# habexpico.net
KiCad netlist of a schematic drawn in EAGLE
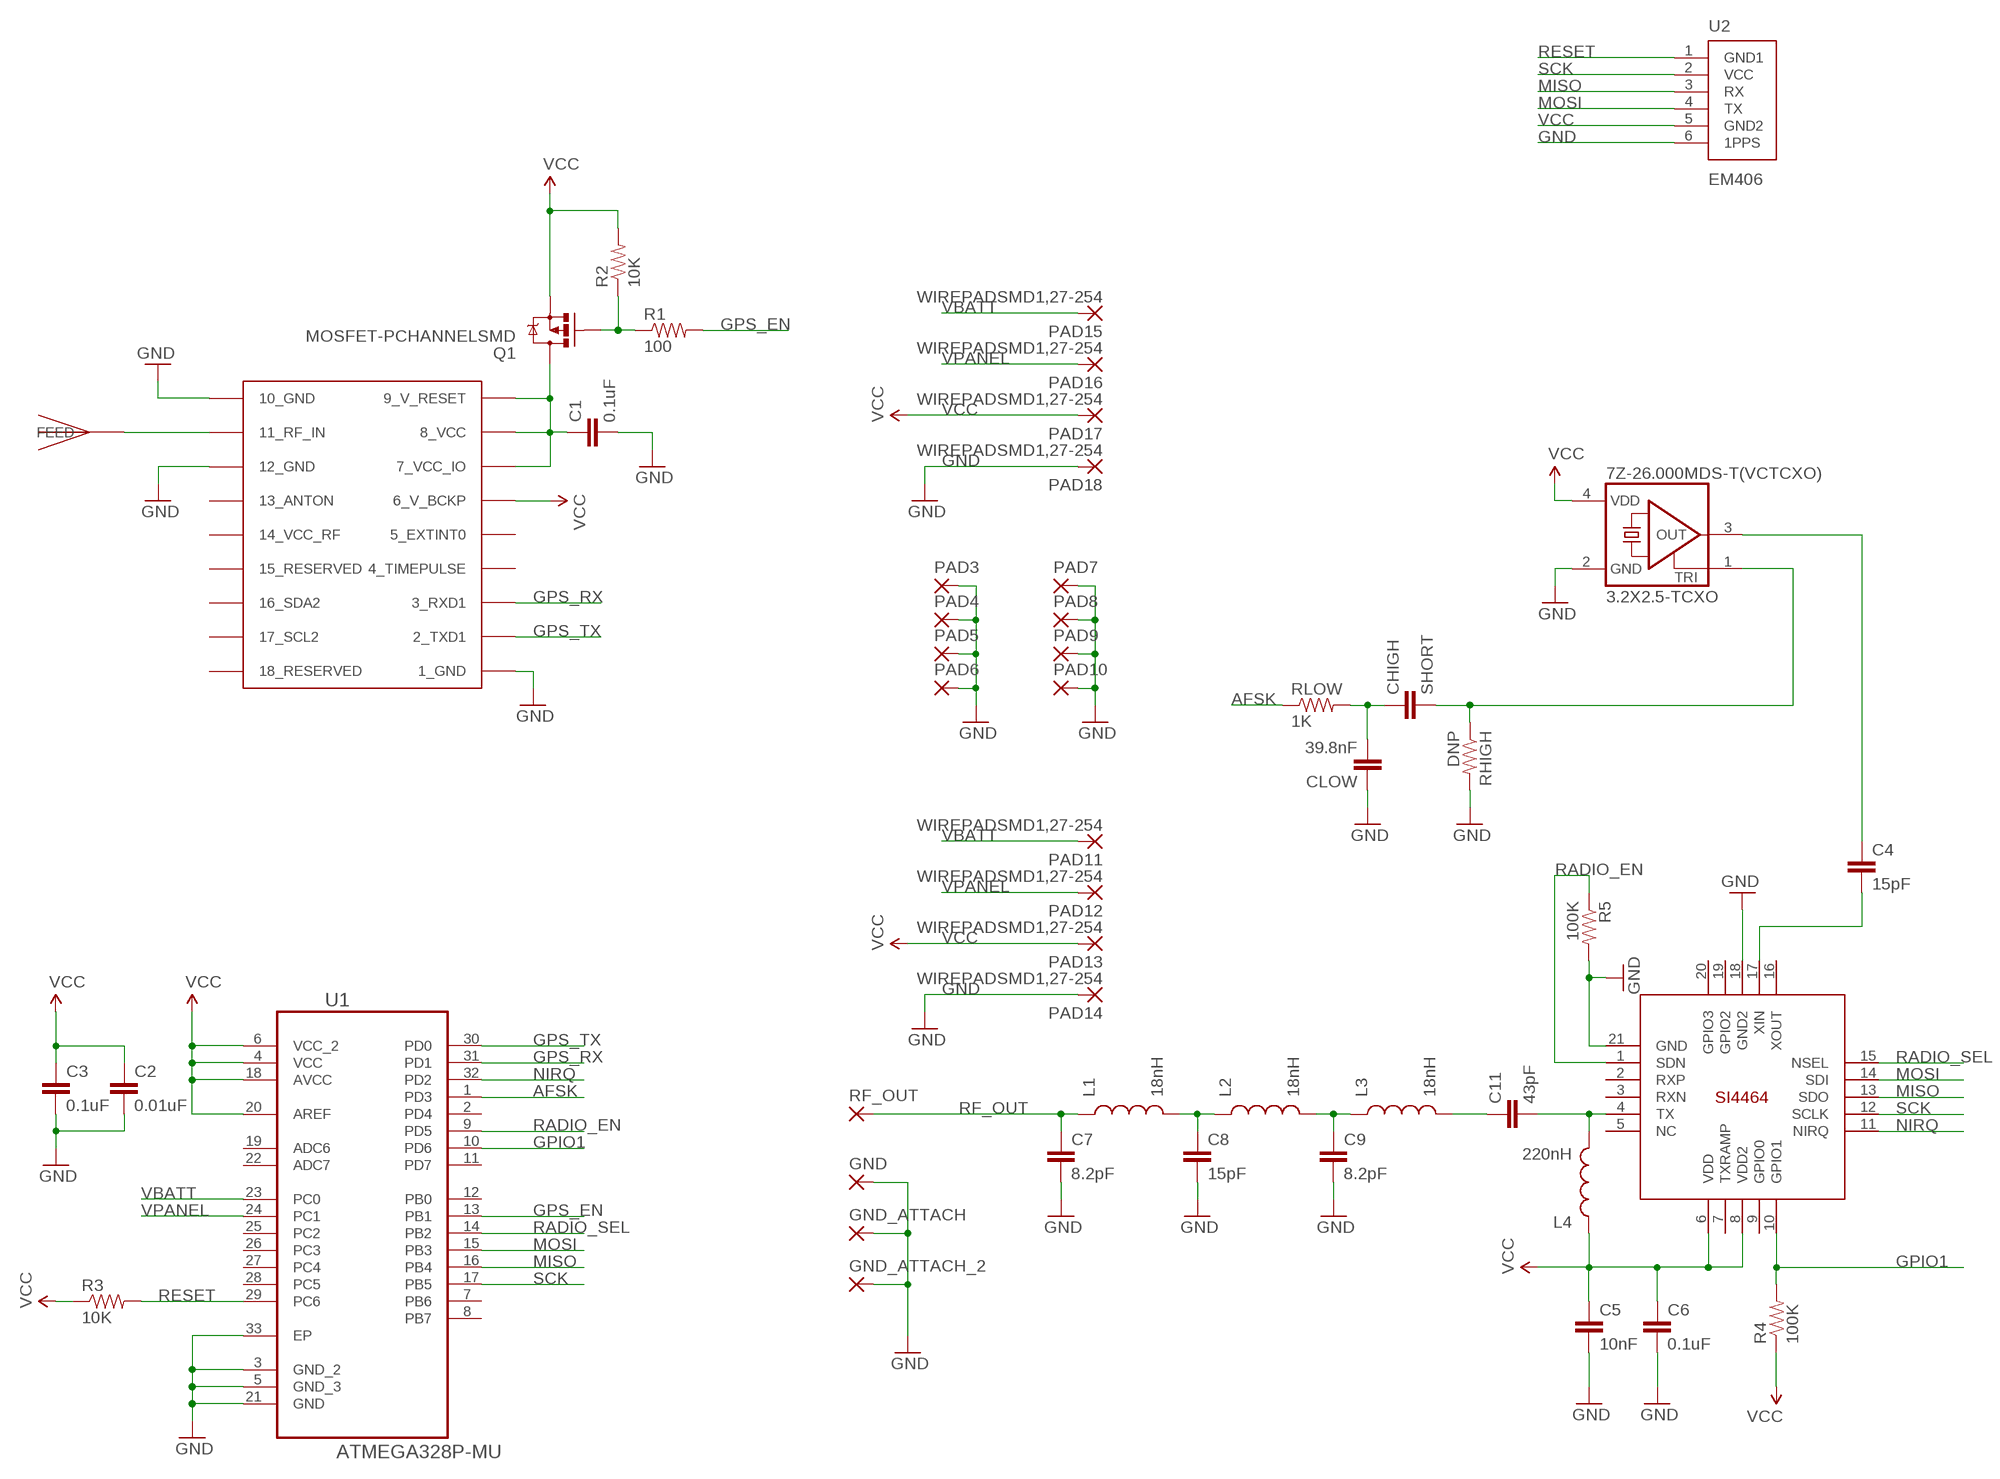
[diagram p0: schematic, sheet 1, part 1 of 2]
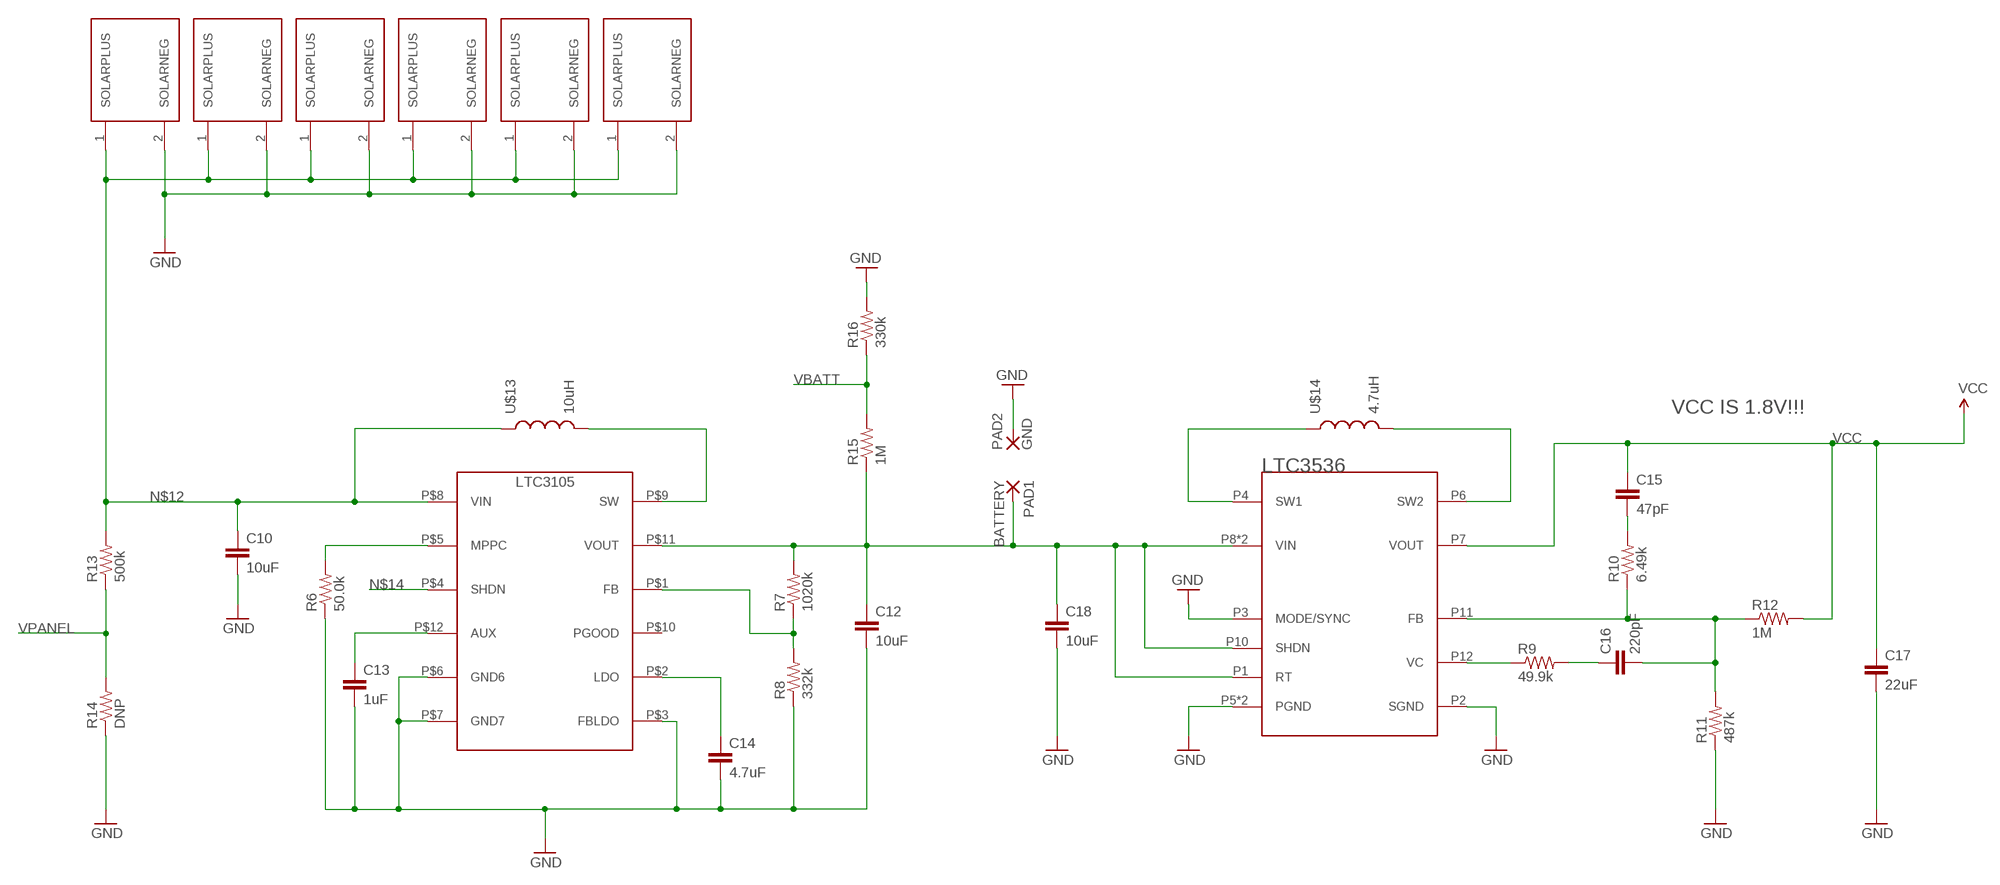
[diagram p1: schematic, sheet 1, part 2 of 2]

(export (version "E")
  (design (tool "Eeschema 10.0.6"))
  (components
    (comp (ref "7Z-26.000MDS-T(VCTCXO)")
      (value "3.2X2.5-TCXO")
      (footprint "eagle-import:3.2X2.5-TCXO")
      (libsource (lib "eagle-import") (part "3.2X2.5-TCXO"))
    )
    (comp (ref "C1")
      (value "0.1uF")
      (footprint "eagle-import:0603-CAP")
      (libsource (lib "eagle-import") (part "CAP0603-CAP"))
    )
    (comp (ref "C2")
      (value "0.01uF")
      (footprint "eagle-import:0603-CAP")
      (libsource (lib "eagle-import") (part "CAP0603-CAP"))
    )
    (comp (ref "C3")
      (value "0.1uF")
      (footprint "eagle-import:0603-CAP")
      (libsource (lib "eagle-import") (part "CAP0603-CAP"))
    )
    (comp (ref "C4")
      (value "15pF")
      (footprint "eagle-import:0603-CAP")
      (libsource (lib "eagle-import") (part "CAP0603-CAP"))
    )
    (comp (ref "C5")
      (value "10nF")
      (footprint "eagle-import:0603-CAP")
      (libsource (lib "eagle-import") (part "CAP0603-CAP"))
    )
    (comp (ref "C6")
      (value "0.1uF")
      (footprint "eagle-import:0603-CAP")
      (libsource (lib "eagle-import") (part "CAP0603-CAP"))
    )
    (comp (ref "C7")
      (value "8.2pF")
      (footprint "eagle-import:0603-CAP")
      (libsource (lib "eagle-import") (part "CAP0603-CAP"))
    )
    (comp (ref "C8")
      (value "15pF")
      (footprint "eagle-import:0603-CAP")
      (libsource (lib "eagle-import") (part "CAP0603-CAP"))
    )
    (comp (ref "C9")
      (value "8.2pF")
      (footprint "eagle-import:0603-CAP")
      (libsource (lib "eagle-import") (part "CAP0603-CAP"))
    )
    (comp (ref "C10")
      (value "10uF")
      (footprint "eagle-import:0805")
      (libsource (lib "eagle-import") (part "CAP0805"))
    )
    (comp (ref "C11")
      (value "43pF")
      (footprint "eagle-import:0603-CAP")
      (libsource (lib "eagle-import") (part "CAP0603-CAP"))
    )
    (comp (ref "C12")
      (value "10uF")
      (footprint "eagle-import:0805")
      (libsource (lib "eagle-import") (part "CAP0805"))
    )
    (comp (ref "C13")
      (value "1uF")
      (footprint "eagle-import:0603-CAP")
      (libsource (lib "eagle-import") (part "CAP0603-CAP"))
    )
    (comp (ref "C14")
      (value "4.7uF")
      (footprint "eagle-import:0603-CAP")
      (libsource (lib "eagle-import") (part "CAP0603-CAP"))
    )
    (comp (ref "C15")
      (value "47pF")
      (footprint "eagle-import:0603-CAP")
      (libsource (lib "eagle-import") (part "CAP0603-CAP"))
    )
    (comp (ref "C16")
      (value "220pF")
      (footprint "eagle-import:0603-CAP")
      (libsource (lib "eagle-import") (part "CAP0603-CAP"))
    )
    (comp (ref "C17")
      (value "22uF")
      (footprint "eagle-import:0603-CAP")
      (libsource (lib "eagle-import") (part "CAP0603-CAP"))
    )
    (comp (ref "C18")
      (value "10uF")
      (footprint "eagle-import:0805")
      (libsource (lib "eagle-import") (part "CAP0805"))
    )
    (comp (ref "CHIGH")
      (value "SHORT")
      (footprint "eagle-import:0603-CAP")
      (libsource (lib "eagle-import") (part "CAP0603-CAP"))
    )
    (comp (ref "CLOW")
      (value "39.8nF")
      (footprint "eagle-import:0603-CAP")
      (libsource (lib "eagle-import") (part "CAP0603-CAP"))
    )
    (comp (ref "GND")
      (value "SMD5")
      (footprint "eagle-import:SMD2,54-5,08")
      (libsource (lib "eagle-import") (part "SMD5"))
    )
    (comp (ref "GND_ATTACH")
      (value "SMD2")
      (footprint "eagle-import:SMD1,27-2,54")
      (libsource (lib "eagle-import") (part "SMD2"))
    )
    (comp (ref "GND_ATTACH_2")
      (value "SMD2")
      (footprint "eagle-import:SMD1,27-2,54")
      (libsource (lib "eagle-import") (part "SMD2"))
    )
    (comp (ref "L1")
      (value "18nH")
      (footprint "eagle-import:0603")
      (libsource (lib "eagle-import") (part "INDUCTOR0603"))
    )
    (comp (ref "L2")
      (value "18nH")
      (footprint "eagle-import:0603")
      (libsource (lib "eagle-import") (part "INDUCTOR0603"))
    )
    (comp (ref "L3")
      (value "18nH")
      (footprint "eagle-import:0603")
      (libsource (lib "eagle-import") (part "INDUCTOR0603"))
    )
    (comp (ref "L4")
      (value "220nH")
      (footprint "eagle-import:0603")
      (libsource (lib "eagle-import") (part "INDUCTOR0603"))
    )
    (comp (ref "PAD1")
      (value "BATTERY")
      (footprint "eagle-import:5-2,5")
      (libsource (lib "eagle-import") (part "WIREPADSMD5-2,5"))
    )
    (comp (ref "PAD2")
      (value "GND")
      (footprint "eagle-import:5-2,5")
      (libsource (lib "eagle-import") (part "WIREPADSMD5-2,5"))
    )
    (comp (ref "PAD3")
      (value "SMD2")
      (footprint "eagle-import:SMD1,27-2,54")
      (libsource (lib "eagle-import") (part "SMD2"))
    )
    (comp (ref "PAD4")
      (value "SMD2")
      (footprint "eagle-import:SMD1,27-2,54")
      (libsource (lib "eagle-import") (part "SMD2"))
    )
    (comp (ref "PAD5")
      (value "SMD2")
      (footprint "eagle-import:SMD1,27-2,54")
      (libsource (lib "eagle-import") (part "SMD2"))
    )
    (comp (ref "PAD6")
      (value "SMD2")
      (footprint "eagle-import:SMD1,27-2,54")
      (libsource (lib "eagle-import") (part "SMD2"))
    )
    (comp (ref "PAD7")
      (value "SMD2")
      (footprint "eagle-import:SMD1,27-2,54")
      (libsource (lib "eagle-import") (part "SMD2"))
    )
    (comp (ref "PAD8")
      (value "SMD2")
      (footprint "eagle-import:SMD1,27-2,54")
      (libsource (lib "eagle-import") (part "SMD2"))
    )
    (comp (ref "PAD9")
      (value "SMD2")
      (footprint "eagle-import:SMD1,27-2,54")
      (libsource (lib "eagle-import") (part "SMD2"))
    )
    (comp (ref "PAD10")
      (value "SMD2")
      (footprint "eagle-import:SMD1,27-2,54")
      (libsource (lib "eagle-import") (part "SMD2"))
    )
    (comp (ref "PAD11")
      (value "WIREPADSMD1,27-254")
      (footprint "eagle-import:SMD1,27-2,54")
      (libsource (lib "eagle-import") (part "WIREPADSMD1,27-254"))
    )
    (comp (ref "PAD12")
      (value "WIREPADSMD1,27-254")
      (footprint "eagle-import:SMD1,27-2,54")
      (libsource (lib "eagle-import") (part "WIREPADSMD1,27-254"))
    )
    (comp (ref "PAD13")
      (value "WIREPADSMD1,27-254")
      (footprint "eagle-import:SMD1,27-2,54")
      (libsource (lib "eagle-import") (part "WIREPADSMD1,27-254"))
    )
    (comp (ref "PAD14")
      (value "WIREPADSMD1,27-254")
      (footprint "eagle-import:SMD1,27-2,54")
      (libsource (lib "eagle-import") (part "WIREPADSMD1,27-254"))
    )
    (comp (ref "PAD15")
      (value "WIREPADSMD1,27-254")
      (footprint "eagle-import:SMD1,27-2,54")
      (libsource (lib "eagle-import") (part "WIREPADSMD1,27-254"))
    )
    (comp (ref "PAD16")
      (value "WIREPADSMD1,27-254")
      (footprint "eagle-import:SMD1,27-2,54")
      (libsource (lib "eagle-import") (part "WIREPADSMD1,27-254"))
    )
    (comp (ref "PAD17")
      (value "WIREPADSMD1,27-254")
      (footprint "eagle-import:SMD1,27-2,54")
      (libsource (lib "eagle-import") (part "WIREPADSMD1,27-254"))
    )
    (comp (ref "PAD18")
      (value "WIREPADSMD1,27-254")
      (footprint "eagle-import:SMD1,27-2,54")
      (libsource (lib "eagle-import") (part "WIREPADSMD1,27-254"))
    )
    (comp (ref "Q1")
      (value "MOSFET-PCHANNELSMD")
      (footprint "eagle-import:SOT23-3")
      (libsource (lib "eagle-import") (part "MOSFET-PCHANNELSMD"))
    )
    (comp (ref "R1")
      (value "100")
      (footprint "eagle-import:0603-RES")
      (libsource (lib "eagle-import") (part "RESISTOR0603-RES"))
    )
    (comp (ref "R2")
      (value "10K")
      (footprint "eagle-import:0603-RES")
      (libsource (lib "eagle-import") (part "RESISTOR0603-RES"))
    )
    (comp (ref "R3")
      (value "10K")
      (footprint "eagle-import:0603-RES")
      (libsource (lib "eagle-import") (part "RESISTOR0603-RES"))
    )
    (comp (ref "R4")
      (value "100K")
      (footprint "eagle-import:0603-RES")
      (libsource (lib "eagle-import") (part "RESISTOR0603-RES"))
    )
    (comp (ref "R5")
      (value "100K")
      (footprint "eagle-import:0603-RES")
      (libsource (lib "eagle-import") (part "RESISTOR0603-RES"))
    )
    (comp (ref "R6")
      (value "50.0k")
      (footprint "eagle-import:0603-RES")
      (libsource (lib "eagle-import") (part "RESISTOR0603-RES"))
    )
    (comp (ref "R7")
      (value "1020k")
      (footprint "eagle-import:0603-RES")
      (libsource (lib "eagle-import") (part "RESISTOR0603-RES"))
    )
    (comp (ref "R8")
      (value "332k")
      (footprint "eagle-import:0603-RES")
      (libsource (lib "eagle-import") (part "RESISTOR0603-RES"))
    )
    (comp (ref "R9")
      (value "49.9k")
      (footprint "eagle-import:0603-RES")
      (libsource (lib "eagle-import") (part "RESISTOR0603-RES"))
    )
    (comp (ref "R10")
      (value "6.49k")
      (footprint "eagle-import:0603-RES")
      (libsource (lib "eagle-import") (part "RESISTOR0603-RES"))
    )
    (comp (ref "R11")
      (value "487k")
      (footprint "eagle-import:0603-RES")
      (libsource (lib "eagle-import") (part "RESISTOR0603-RES"))
    )
    (comp (ref "R12")
      (value "1M")
      (footprint "eagle-import:0603-RES")
      (libsource (lib "eagle-import") (part "RESISTOR0603-RES"))
    )
    (comp (ref "R13")
      (value "500k")
      (footprint "eagle-import:0603-RES")
      (libsource (lib "eagle-import") (part "RESISTOR0603-RES"))
    )
    (comp (ref "R14")
      (value "DNP")
      (footprint "eagle-import:0603-RES")
      (libsource (lib "eagle-import") (part "RESISTOR0603-RES"))
    )
    (comp (ref "R15")
      (value "1M")
      (footprint "eagle-import:0603-RES")
      (libsource (lib "eagle-import") (part "RESISTOR0603-RES"))
    )
    (comp (ref "R16")
      (value "330k")
      (footprint "eagle-import:0603-RES")
      (libsource (lib "eagle-import") (part "RESISTOR0603-RES"))
    )
    (comp (ref "RF_OUT")
      (value "SMD5")
      (footprint "eagle-import:SMD2,54-5,08")
      (libsource (lib "eagle-import") (part "SMD5"))
    )
    (comp (ref "RHIGH")
      (value "DNP")
      (footprint "eagle-import:0603-RES")
      (libsource (lib "eagle-import") (part "RESISTOR0603-RES"))
    )
    (comp (ref "RLOW")
      (value "1K")
      (footprint "eagle-import:0603-RES")
      (libsource (lib "eagle-import") (part "RESISTOR0603-RES"))
    )
    (comp (ref "U$1")
      (value "SI4464")
      (footprint "eagle-import:QFN20+GNDPAD")
      (libsource (lib "eagle-import") (part "SI4464"))
    )
    (comp (ref "U$2")
      (value "UBLOX_MAX")
      (footprint "eagle-import:UBLOX_MAX")
      (libsource (lib "eagle-import") (part "UBLOX_MAX"))
    )
    (comp (ref "U$4")
      (value "JTI_ANTENNA-1575AT43A40")
      (footprint "eagle-import:JTI_ANTENNA-1575AT43A40")
      (libsource (lib "eagle-import") (part "JTI_ANTENNA-1575AT43A40"))
    )
    (comp (ref "U$5")
      (value "LTC3105")
      (footprint "eagle-import:LTC3105")
      (libsource (lib "eagle-import") (part "LTC3105"))
    )
    (comp (ref "U$6")
      (value "LTC3536")
      (footprint "eagle-import:LTC3536-MSE")
      (libsource (lib "eagle-import") (part "LTC3536"))
    )
    (comp (ref "U$7")
      (value "KXOB22-12X1")
      (footprint "eagle-import:KXOB22-12X1")
      (libsource (lib "eagle-import") (part "KXOB22-12X1"))
    )
    (comp (ref "U$8")
      (value "KXOB22-12X1")
      (footprint "eagle-import:KXOB22-12X1")
      (libsource (lib "eagle-import") (part "KXOB22-12X1"))
    )
    (comp (ref "U$9")
      (value "KXOB22-12X1")
      (footprint "eagle-import:KXOB22-12X1")
      (libsource (lib "eagle-import") (part "KXOB22-12X1"))
    )
    (comp (ref "U$10")
      (value "KXOB22-12X1")
      (footprint "eagle-import:KXOB22-12X1")
      (libsource (lib "eagle-import") (part "KXOB22-12X1"))
    )
    (comp (ref "U$11")
      (value "KXOB22-12X1")
      (footprint "eagle-import:KXOB22-12X1")
      (libsource (lib "eagle-import") (part "KXOB22-12X1"))
    )
    (comp (ref "U$12")
      (value "KXOB22-12X1")
      (footprint "eagle-import:KXOB22-12X1")
      (libsource (lib "eagle-import") (part "KXOB22-12X1"))
    )
    (comp (ref "U$13")
      (value "10uH")
      (footprint "eagle-import:COILCRAFT_MSS5131")
      (libsource (lib "eagle-import") (part "COILCRAFT-MSS5131"))
    )
    (comp (ref "U$14")
      (value "4.7uH")
      (footprint "eagle-import:COILCRAFT_MSS5131")
      (libsource (lib "eagle-import") (part "COILCRAFT-MSS5131"))
    )
    (comp (ref "U1")
      (value "ATMEGA328P-MU")
      (footprint "eagle-import:QFN50P500X500X100-33N")
      (libsource (lib "eagle-import") (part "ATMEGA328P-MU"))
    )
    (comp (ref "U2")
      (value "EM406")
      (footprint "eagle-import:EM406")
      (libsource (lib "eagle-import") (part "EM406"))
    )
  )
  (nets
    (net (code "1") (name "/AFSK") (class "Default")
      (node (ref "RLOW") (pin "1") (pinfunction "1_1") (pintype "passive"))
      (node (ref "U1") (pin "1") (pinfunction "PD3_1") (pintype "bidirectional"))
    )
    (net (code "2") (name "/GPIO1") (class "Default")
      (node (ref "R4") (pin "2") (pinfunction "2_2") (pintype "passive"))
      (node (ref "U$1") (pin "10") (pinfunction "GPIO1_10") (pintype "bidirectional"))
      (node (ref "U1") (pin "10") (pinfunction "PD6_10") (pintype "bidirectional"))
    )
    (net (code "3") (name "/GPS_EN") (class "Default")
      (node (ref "R1") (pin "2") (pinfunction "2_2") (pintype "passive"))
      (node (ref "U1") (pin "13") (pinfunction "PB1_13") (pintype "bidirectional"))
    )
    (net (code "4") (name "/GPS_RX") (class "Default")
      (node (ref "U$2") (pin "3_RXD1") (pinfunction "3_RXD1_3_RXD1") (pintype "bidirectional"))
      (node (ref "U1") (pin "31") (pinfunction "PD1_31") (pintype "bidirectional"))
    )
    (net (code "5") (name "/GPS_TX") (class "Default")
      (node (ref "U$2") (pin "2_TXD1") (pinfunction "2_TXD1_2_TXD1") (pintype "bidirectional"))
      (node (ref "U1") (pin "30") (pinfunction "PD0_30") (pintype "bidirectional"))
    )
    (net (code "6") (name "/MISO") (class "Default")
      (node (ref "U$1") (pin "13") (pinfunction "SDO_13") (pintype "bidirectional"))
      (node (ref "U1") (pin "16") (pinfunction "PB4_16") (pintype "bidirectional"))
      (node (ref "U2") (pin "3") (pinfunction "RX_3") (pintype "bidirectional"))
    )
    (net (code "7") (name "/MOSI") (class "Default")
      (node (ref "U$1") (pin "14") (pinfunction "SDI_14") (pintype "bidirectional"))
      (node (ref "U1") (pin "15") (pinfunction "PB3_15") (pintype "bidirectional"))
      (node (ref "U2") (pin "4") (pinfunction "TX_4") (pintype "bidirectional"))
    )
    (net (code "8") (name "/N$12") (class "Default")
      (node (ref "C10") (pin "1") (pinfunction "1_1") (pintype "passive"))
      (node (ref "R13") (pin "2") (pinfunction "2_2") (pintype "passive"))
      (node (ref "U$10") (pin "1") (pinfunction "SOLARPLUS_1") (pintype "bidirectional"))
      (node (ref "U$11") (pin "1") (pinfunction "SOLARPLUS_1") (pintype "bidirectional"))
      (node (ref "U$12") (pin "1") (pinfunction "SOLARPLUS_1") (pintype "bidirectional"))
      (node (ref "U$13") (pin "P$2") (pinfunction "1_P$2") (pintype "passive"))
      (node (ref "U$5") (pin "P$8") (pinfunction "VIN_P$8") (pintype "bidirectional"))
      (node (ref "U$7") (pin "1") (pinfunction "SOLARPLUS_1") (pintype "bidirectional"))
      (node (ref "U$8") (pin "1") (pinfunction "SOLARPLUS_1") (pintype "bidirectional"))
      (node (ref "U$9") (pin "1") (pinfunction "SOLARPLUS_1") (pintype "bidirectional"))
    )
    (net (code "9") (name "/N$14") (class "Default")
      (node (ref "U$5") (pin "P$4") (pinfunction "SHDN_P$4") (pintype "bidirectional"))
    )
    (net (code "10") (name "/NIRQ") (class "Default")
      (node (ref "U$1") (pin "11") (pinfunction "NIRQ_11") (pintype "bidirectional"))
      (node (ref "U1") (pin "32") (pinfunction "PD2_32") (pintype "bidirectional"))
    )
    (net (code "11") (name "/RADIO_EN") (class "Default")
      (node (ref "R5") (pin "1") (pinfunction "1_1") (pintype "passive"))
      (node (ref "U$1") (pin "1") (pinfunction "SDN_1") (pintype "bidirectional"))
      (node (ref "U1") (pin "9") (pinfunction "PD5_9") (pintype "bidirectional"))
    )
    (net (code "12") (name "/RADIO_SEL") (class "Default")
      (node (ref "U$1") (pin "15") (pinfunction "NSEL_15") (pintype "bidirectional"))
      (node (ref "U1") (pin "14") (pinfunction "PB2_14") (pintype "bidirectional"))
    )
    (net (code "13") (name "/RESET") (class "Default")
      (node (ref "R3") (pin "2") (pinfunction "2_2") (pintype "passive"))
      (node (ref "U1") (pin "29") (pinfunction "PC6_29") (pintype "bidirectional"))
      (node (ref "U2") (pin "1") (pinfunction "GND1_1") (pintype "bidirectional"))
    )
    (net (code "14") (name "/RF_OUT") (class "Default")
      (node (ref "C7") (pin "1") (pinfunction "1_1") (pintype "passive"))
      (node (ref "L1") (pin "1") (pinfunction "1_1") (pintype "passive"))
      (node (ref "RF_OUT") (pin "1") (pinfunction "P_1") (pintype "passive"))
    )
    (net (code "15") (name "/SCK") (class "Default")
      (node (ref "U$1") (pin "12") (pinfunction "SCLK_12") (pintype "bidirectional"))
      (node (ref "U1") (pin "17") (pinfunction "PB5_17") (pintype "bidirectional"))
      (node (ref "U2") (pin "2") (pinfunction "VCC_2") (pintype "bidirectional"))
    )
    (net (code "16") (name "/VBATT") (class "Default")
      (node (ref "PAD11") (pin "1") (pinfunction "P_1") (pintype "passive"))
      (node (ref "PAD15") (pin "1") (pinfunction "P_1") (pintype "passive"))
      (node (ref "R15") (pin "2") (pinfunction "2_2") (pintype "passive"))
      (node (ref "R16") (pin "1") (pinfunction "1_1") (pintype "passive"))
      (node (ref "U1") (pin "23") (pinfunction "PC0_23") (pintype "bidirectional"))
    )
    (net (code "17") (name "/VPANEL") (class "Default")
      (node (ref "PAD12") (pin "1") (pinfunction "P_1") (pintype "passive"))
      (node (ref "PAD16") (pin "1") (pinfunction "P_1") (pintype "passive"))
      (node (ref "R13") (pin "1") (pinfunction "1_1") (pintype "passive"))
      (node (ref "R14") (pin "2") (pinfunction "2_2") (pintype "passive"))
      (node (ref "U1") (pin "24") (pinfunction "PC1_24") (pintype "bidirectional"))
    )
    (net (code "18") (name "GND") (class "Default")
      (node (ref "7Z-26.000MDS-T(VCTCXO)") (pin "2") (pinfunction "GND_2") (pintype "power_in"))
      (node (ref "C1") (pin "2") (pinfunction "2_2") (pintype "passive"))
      (node (ref "C10") (pin "2") (pinfunction "2_2") (pintype "passive"))
      (node (ref "C12") (pin "2") (pinfunction "2_2") (pintype "passive"))
      (node (ref "C13") (pin "2") (pinfunction "2_2") (pintype "passive"))
      (node (ref "C14") (pin "2") (pinfunction "2_2") (pintype "passive"))
      (node (ref "C17") (pin "2") (pinfunction "2_2") (pintype "passive"))
      (node (ref "C18") (pin "2") (pinfunction "2_2") (pintype "passive"))
      (node (ref "C2") (pin "2") (pinfunction "2_2") (pintype "passive"))
      (node (ref "C3") (pin "2") (pinfunction "2_2") (pintype "passive"))
      (node (ref "C5") (pin "2") (pinfunction "2_2") (pintype "passive"))
      (node (ref "C6") (pin "2") (pinfunction "2_2") (pintype "passive"))
      (node (ref "C7") (pin "2") (pinfunction "2_2") (pintype "passive"))
      (node (ref "C8") (pin "2") (pinfunction "2_2") (pintype "passive"))
      (node (ref "C9") (pin "2") (pinfunction "2_2") (pintype "passive"))
      (node (ref "CLOW") (pin "1") (pinfunction "1_1") (pintype "passive"))
      (node (ref "GND") (pin "1") (pinfunction "P_1") (pintype "passive"))
      (node (ref "GND_ATTACH") (pin "1") (pinfunction "P_1") (pintype "passive"))
      (node (ref "GND_ATTACH_2") (pin "1") (pinfunction "P_1") (pintype "passive"))
      (node (ref "PAD10") (pin "1") (pinfunction "P_1") (pintype "passive"))
      (node (ref "PAD14") (pin "1") (pinfunction "P_1") (pintype "passive"))
      (node (ref "PAD18") (pin "1") (pinfunction "P_1") (pintype "passive"))
      (node (ref "PAD2") (pin "1") (pinfunction "P_1") (pintype "passive"))
      (node (ref "PAD3") (pin "1") (pinfunction "P_1") (pintype "passive"))
      (node (ref "PAD4") (pin "1") (pinfunction "P_1") (pintype "passive"))
      (node (ref "PAD5") (pin "1") (pinfunction "P_1") (pintype "passive"))
      (node (ref "PAD6") (pin "1") (pinfunction "P_1") (pintype "passive"))
      (node (ref "PAD7") (pin "1") (pinfunction "P_1") (pintype "passive"))
      (node (ref "PAD8") (pin "1") (pinfunction "P_1") (pintype "passive"))
      (node (ref "PAD9") (pin "1") (pinfunction "P_1") (pintype "passive"))
      (node (ref "R11") (pin "1") (pinfunction "1_1") (pintype "passive"))
      (node (ref "R14") (pin "1") (pinfunction "1_1") (pintype "passive"))
      (node (ref "R16") (pin "2") (pinfunction "2_2") (pintype "passive"))
      (node (ref "R5") (pin "2") (pinfunction "2_2") (pintype "passive"))
      (node (ref "R6") (pin "1") (pinfunction "1_1") (pintype "passive"))
      (node (ref "R8") (pin "1") (pinfunction "1_1") (pintype "passive"))
      (node (ref "RHIGH") (pin "2") (pinfunction "2_2") (pintype "passive"))
      (node (ref "U$1") (pin "18") (pinfunction "GND2_18") (pintype "bidirectional"))
      (node (ref "U$1") (pin "21") (pinfunction "GND_21") (pintype "bidirectional"))
      (node (ref "U$10") (pin "2") (pinfunction "SOLARNEG_2") (pintype "bidirectional"))
      (node (ref "U$11") (pin "2") (pinfunction "SOLARNEG_2") (pintype "bidirectional"))
      (node (ref "U$12") (pin "2") (pinfunction "SOLARNEG_2") (pintype "bidirectional"))
      (node (ref "U$2") (pin "10_GND") (pinfunction "10_GND_10_GND") (pintype "power_in"))
      (node (ref "U$2") (pin "12_GND") (pinfunction "12_GND_12_GND") (pintype "power_in"))
      (node (ref "U$2") (pin "1_GND") (pinfunction "1_GND_1_GND") (pintype "power_in"))
      (node (ref "U$5") (pin "P$3") (pinfunction "FBLDO_P$3") (pintype "bidirectional"))
      (node (ref "U$5") (pin "P$6") (pinfunction "GND6_P$6") (pintype "bidirectional"))
      (node (ref "U$5") (pin "P$7") (pinfunction "GND7_P$7") (pintype "bidirectional"))
      (node (ref "U$6") (pin "P13") (pinfunction "PGND_P13") (pintype "bidirectional"))
      (node (ref "U$6") (pin "P2") (pinfunction "SGND_P2") (pintype "bidirectional"))
      (node (ref "U$6") (pin "P3") (pinfunction "MODE/SYNC_P3") (pintype "bidirectional"))
      (node (ref "U$6") (pin "P5") (pinfunction "PGND_P5") (pintype "bidirectional"))
      (node (ref "U$7") (pin "2") (pinfunction "SOLARNEG_2") (pintype "bidirectional"))
      (node (ref "U$8") (pin "2") (pinfunction "SOLARNEG_2") (pintype "bidirectional"))
      (node (ref "U$9") (pin "2") (pinfunction "SOLARNEG_2") (pintype "bidirectional"))
      (node (ref "U1") (pin "21") (pinfunction "GND_21") (pintype "passive"))
      (node (ref "U1") (pin "3") (pinfunction "GND_2_3") (pintype "passive"))
      (node (ref "U1") (pin "33") (pinfunction "EP_33") (pintype "passive"))
      (node (ref "U1") (pin "5") (pinfunction "GND_3_5") (pintype "passive"))
      (node (ref "U2") (pin "6") (pinfunction "1PPS_6") (pintype "bidirectional"))
    )
    (net (code "19") (name "Net-(7Z-26.000MDS-T(VCTCXO)-OUT)") (class "Default")
      (node (ref "7Z-26.000MDS-T(VCTCXO)") (pin "3") (pinfunction "OUT_3") (pintype "output"))
      (node (ref "C4") (pin "1") (pinfunction "1_1") (pintype "passive"))
    )
    (net (code "20") (name "Net-(7Z-26.000MDS-T(VCTCXO)-TRI)") (class "Default")
      (node (ref "7Z-26.000MDS-T(VCTCXO)") (pin "1") (pinfunction "TRI_1") (pintype "input"))
      (node (ref "CHIGH") (pin "2") (pinfunction "2_2") (pintype "passive"))
      (node (ref "RHIGH") (pin "1") (pinfunction "1_1") (pintype "passive"))
    )
    (net (code "21") (name "Net-(C8-Pad1)") (class "Default")
      (node (ref "C8") (pin "1") (pinfunction "1_1") (pintype "passive"))
      (node (ref "L1") (pin "2") (pinfunction "2_2") (pintype "passive"))
      (node (ref "L2") (pin "1") (pinfunction "1_1") (pintype "passive"))
    )
    (net (code "22") (name "Net-(C9-Pad1)") (class "Default")
      (node (ref "C9") (pin "1") (pinfunction "1_1") (pintype "passive"))
      (node (ref "L2") (pin "2") (pinfunction "2_2") (pintype "passive"))
      (node (ref "L3") (pin "1") (pinfunction "1_1") (pintype "passive"))
    )
    (net (code "23") (name "Net-(C11-Pad1)") (class "Default")
      (node (ref "C11") (pin "1") (pinfunction "1_1") (pintype "passive"))
      (node (ref "L3") (pin "2") (pinfunction "2_2") (pintype "passive"))
    )
    (net (code "24") (name "Net-(C15-Pad2)") (class "Default")
      (node (ref "C15") (pin "2") (pinfunction "2_2") (pintype "passive"))
      (node (ref "R10") (pin "2") (pinfunction "2_2") (pintype "passive"))
    )
    (net (code "25") (name "Net-(C16-Pad1)") (class "Default")
      (node (ref "C16") (pin "1") (pinfunction "1_1") (pintype "passive"))
      (node (ref "R9") (pin "2") (pinfunction "2_2") (pintype "passive"))
    )
    (net (code "26") (name "Net-(CHIGH-Pad1)") (class "Default")
      (node (ref "CHIGH") (pin "1") (pinfunction "1_1") (pintype "passive"))
      (node (ref "CLOW") (pin "2") (pinfunction "2_2") (pintype "passive"))
      (node (ref "RLOW") (pin "2") (pinfunction "2_2") (pintype "passive"))
    )
    (net (code "27") (name "Net-(PAD1-P)") (class "Default")
      (node (ref "C12") (pin "1") (pinfunction "1_1") (pintype "passive"))
      (node (ref "C18") (pin "1") (pinfunction "1_1") (pintype "passive"))
      (node (ref "PAD1") (pin "1") (pinfunction "P_1") (pintype "passive"))
      (node (ref "R15") (pin "1") (pinfunction "1_1") (pintype "passive"))
      (node (ref "R7") (pin "2") (pinfunction "2_2") (pintype "passive"))
      (node (ref "U$5") (pin "P$11") (pinfunction "VOUT_P$11") (pintype "bidirectional"))
      (node (ref "U$6") (pin "P1") (pinfunction "RT_P1") (pintype "bidirectional"))
      (node (ref "U$6") (pin "P10") (pinfunction "SHDN_P10") (pintype "bidirectional"))
      (node (ref "U$6") (pin "P8") (pinfunction "VIN_P8") (pintype "bidirectional"))
      (node (ref "U$6") (pin "P9") (pinfunction "VIN_P9") (pintype "bidirectional"))
    )
    (net (code "28") (name "Net-(Q1-D)") (class "Default")
      (node (ref "C1") (pin "1") (pinfunction "1_1") (pintype "passive"))
      (node (ref "Q1") (pin "3") (pinfunction "D_3") (pintype "passive"))
      (node (ref "U$2") (pin "7_VCC_IO") (pinfunction "7_VCC_IO_7_VCC_IO") (pintype "power_in"))
      (node (ref "U$2") (pin "8_VCC") (pinfunction "8_VCC_8_VCC") (pintype "power_in"))
      (node (ref "U$2") (pin "9_V_RESET") (pinfunction "9_V_RESET_9_V_RESET") (pintype "power_in"))
    )
    (net (code "29") (name "Net-(Q1-G)") (class "Default")
      (node (ref "Q1") (pin "1") (pinfunction "G_1") (pintype "passive"))
      (node (ref "R1") (pin "1") (pinfunction "1_1") (pintype "passive"))
      (node (ref "R2") (pin "1") (pinfunction "1_1") (pintype "passive"))
    )
    (net (code "30") (name "Net-(U$1-TX)") (class "Default")
      (node (ref "C11") (pin "2") (pinfunction "2_2") (pintype "passive"))
      (node (ref "L4") (pin "2") (pinfunction "2_2") (pintype "passive"))
      (node (ref "U$1") (pin "4") (pinfunction "TX_4") (pintype "bidirectional"))
    )
    (net (code "31") (name "Net-(U$1-XIN)") (class "Default")
      (node (ref "C4") (pin "2") (pinfunction "2_2") (pintype "passive"))
      (node (ref "U$1") (pin "17") (pinfunction "XIN_17") (pintype "bidirectional"))
    )
    (net (code "32") (name "Net-(U$2-Pad11_RF_IN)") (class "Default")
      (node (ref "U$2") (pin "11_RF_IN") (pinfunction "11_RF_IN_11_RF_IN") (pintype "bidirectional"))
      (node (ref "U$4") (pin "FEED") (pinfunction "FEED_FEED") (pintype "bidirectional"))
    )
    (net (code "33") (name "Net-(U$5-AUX)") (class "Default")
      (node (ref "C13") (pin "1") (pinfunction "1_1") (pintype "passive"))
      (node (ref "U$5") (pin "P$12") (pinfunction "AUX_P$12") (pintype "bidirectional"))
    )
    (net (code "34") (name "Net-(U$5-FB)") (class "Default")
      (node (ref "R7") (pin "1") (pinfunction "1_1") (pintype "passive"))
      (node (ref "R8") (pin "2") (pinfunction "2_2") (pintype "passive"))
      (node (ref "U$5") (pin "P$1") (pinfunction "FB_P$1") (pintype "bidirectional"))
    )
    (net (code "35") (name "Net-(U$5-LDO)") (class "Default")
      (node (ref "C14") (pin "1") (pinfunction "1_1") (pintype "passive"))
      (node (ref "U$5") (pin "P$2") (pinfunction "LDO_P$2") (pintype "bidirectional"))
    )
    (net (code "36") (name "Net-(U$5-MPPC)") (class "Default")
      (node (ref "R6") (pin "2") (pinfunction "2_2") (pintype "passive"))
      (node (ref "U$5") (pin "P$5") (pinfunction "MPPC_P$5") (pintype "bidirectional"))
    )
    (net (code "37") (name "Net-(U$6-FB)") (class "Default")
      (node (ref "C16") (pin "2") (pinfunction "2_2") (pintype "passive"))
      (node (ref "R10") (pin "1") (pinfunction "1_1") (pintype "passive"))
      (node (ref "R11") (pin "2") (pinfunction "2_2") (pintype "passive"))
      (node (ref "R12") (pin "1") (pinfunction "1_1") (pintype "passive"))
      (node (ref "U$6") (pin "P11") (pinfunction "FB_P11") (pintype "bidirectional"))
    )
    (net (code "38") (name "Net-(U$6-VC)") (class "Default")
      (node (ref "R9") (pin "1") (pinfunction "1_1") (pintype "passive"))
      (node (ref "U$6") (pin "P12") (pinfunction "VC_P12") (pintype "bidirectional"))
    )
    (net (code "39") (name "Net-(U$13-2)") (class "Default")
      (node (ref "U$13") (pin "P$1") (pinfunction "2_P$1") (pintype "passive"))
      (node (ref "U$5") (pin "P$9") (pinfunction "SW_P$9") (pintype "bidirectional"))
    )
    (net (code "40") (name "Net-(U$14-1)") (class "Default")
      (node (ref "U$14") (pin "P$2") (pinfunction "1_P$2") (pintype "passive"))
      (node (ref "U$6") (pin "P4") (pinfunction "SW1_P4") (pintype "bidirectional"))
    )
    (net (code "41") (name "Net-(U$14-2)") (class "Default")
      (node (ref "U$14") (pin "P$1") (pinfunction "2_P$1") (pintype "passive"))
      (node (ref "U$6") (pin "P6") (pinfunction "SW2_P6") (pintype "bidirectional"))
    )
    (net (code "42") (name "VCC") (class "Default")
      (node (ref "7Z-26.000MDS-T(VCTCXO)") (pin "4") (pinfunction "VDD_4") (pintype "power_in"))
      (node (ref "C15") (pin "1") (pinfunction "1_1") (pintype "passive"))
      (node (ref "C17") (pin "1") (pinfunction "1_1") (pintype "passive"))
      (node (ref "C2") (pin "1") (pinfunction "1_1") (pintype "passive"))
      (node (ref "C3") (pin "1") (pinfunction "1_1") (pintype "passive"))
      (node (ref "C5") (pin "1") (pinfunction "1_1") (pintype "passive"))
      (node (ref "C6") (pin "1") (pinfunction "1_1") (pintype "passive"))
      (node (ref "L4") (pin "1") (pinfunction "1_1") (pintype "passive"))
      (node (ref "PAD13") (pin "1") (pinfunction "P_1") (pintype "passive"))
      (node (ref "PAD17") (pin "1") (pinfunction "P_1") (pintype "passive"))
      (node (ref "Q1") (pin "2") (pinfunction "S_2") (pintype "passive"))
      (node (ref "R12") (pin "2") (pinfunction "2_2") (pintype "passive"))
      (node (ref "R2") (pin "2") (pinfunction "2_2") (pintype "passive"))
      (node (ref "R3") (pin "1") (pinfunction "1_1") (pintype "passive"))
      (node (ref "R4") (pin "1") (pinfunction "1_1") (pintype "passive"))
      (node (ref "U$1") (pin "6") (pinfunction "VDD_6") (pintype "bidirectional"))
      (node (ref "U$1") (pin "8") (pinfunction "VDD2_8") (pintype "bidirectional"))
      (node (ref "U$2") (pin "6_V_BCKP") (pinfunction "6_V_BCKP_6_V_BCKP") (pintype "bidirectional"))
      (node (ref "U$6") (pin "P7") (pinfunction "VOUT_P7") (pintype "bidirectional"))
      (node (ref "U1") (pin "18") (pinfunction "AVCC_18") (pintype "power_in"))
      (node (ref "U1") (pin "20") (pinfunction "AREF_20") (pintype "input"))
      (node (ref "U1") (pin "4") (pinfunction "VCC_4") (pintype "power_in"))
      (node (ref "U1") (pin "6") (pinfunction "VCC_2_6") (pintype "power_in"))
      (node (ref "U2") (pin "5") (pinfunction "GND2_5") (pintype "bidirectional"))
    )
    (net (code "43") (name "unconnected-(U$1-GPIO0-Pad9)") (class "Default")
      (node (ref "U$1") (pin "9") (pinfunction "GPIO0_9") (pintype "bidirectional"))
    )
    (net (code "44") (name "unconnected-(U$1-GPIO2-Pad19)") (class "Default")
      (node (ref "U$1") (pin "19") (pinfunction "GPIO2_19") (pintype "bidirectional"))
    )
    (net (code "45") (name "unconnected-(U$1-GPIO3-Pad20)") (class "Default")
      (node (ref "U$1") (pin "20") (pinfunction "GPIO3_20") (pintype "bidirectional"))
    )
    (net (code "46") (name "unconnected-(U$1-NC -Pad5)") (class "Default")
      (node (ref "U$1") (pin "5") (pinfunction "NC _5") (pintype "bidirectional"))
    )
    (net (code "47") (name "unconnected-(U$1-RXN-Pad3)") (class "Default")
      (node (ref "U$1") (pin "3") (pinfunction "RXN_3") (pintype "bidirectional"))
    )
    (net (code "48") (name "unconnected-(U$1-RXP-Pad2)") (class "Default")
      (node (ref "U$1") (pin "2") (pinfunction "RXP_2") (pintype "bidirectional"))
    )
    (net (code "49") (name "unconnected-(U$1-TXRAMP-Pad7)") (class "Default")
      (node (ref "U$1") (pin "7") (pinfunction "TXRAMP_7") (pintype "bidirectional"))
    )
    (net (code "50") (name "unconnected-(U$1-XOUT-Pad16)") (class "Default")
      (node (ref "U$1") (pin "16") (pinfunction "XOUT_16") (pintype "bidirectional"))
    )
    (net (code "51") (name "unconnected-(U$2-Pad4_TIMEPULSE)") (class "Default")
      (node (ref "U$2") (pin "4_TIMEPULSE") (pinfunction "4_TIMEPULSE_4_TIMEPULSE") (pintype "bidirectional"))
    )
    (net (code "52") (name "unconnected-(U$2-Pad5_EXTINT0)") (class "Default")
      (node (ref "U$2") (pin "5_EXTINT0") (pinfunction "5_EXTINT0_5_EXTINT0") (pintype "bidirectional"))
    )
    (net (code "53") (name "unconnected-(U$2-Pad13_ANTON)") (class "Default")
      (node (ref "U$2") (pin "13_ANTON") (pinfunction "13_ANTON_13_ANTON") (pintype "bidirectional"))
    )
    (net (code "54") (name "unconnected-(U$2-Pad14_VCC_RF)") (class "Default")
      (node (ref "U$2") (pin "14_VCC_RF") (pinfunction "14_VCC_RF_14_VCC_RF") (pintype "bidirectional"))
    )
    (net (code "55") (name "unconnected-(U$2-Pad15_RESERVED)") (class "Default")
      (node (ref "U$2") (pin "15_RESERVED") (pinfunction "15_RESERVED_15_RESERVED") (pintype "bidirectional"))
    )
    (net (code "56") (name "unconnected-(U$2-Pad16_SDA2)") (class "Default")
      (node (ref "U$2") (pin "16_SDA2") (pinfunction "16_SDA2_16_SDA2") (pintype "bidirectional"))
    )
    (net (code "57") (name "unconnected-(U$2-Pad17_SCL2)") (class "Default")
      (node (ref "U$2") (pin "17_SCL2") (pinfunction "17_SCL2_17_SCL2") (pintype "bidirectional"))
    )
    (net (code "58") (name "unconnected-(U$2-Pad18_RESERVED)") (class "Default")
      (node (ref "U$2") (pin "18_RESERVED") (pinfunction "18_RESERVED_18_RESERVED") (pintype "bidirectional"))
    )
    (net (code "59") (name "unconnected-(U$5-PGOOD-PadP$10)") (class "Default")
      (node (ref "U$5") (pin "P$10") (pinfunction "PGOOD_P$10") (pintype "bidirectional"))
    )
    (net (code "60") (name "unconnected-(U1-ADC6-Pad19)") (class "Default")
      (node (ref "U1") (pin "19") (pinfunction "ADC6_19") (pintype "input"))
    )
    (net (code "61") (name "unconnected-(U1-ADC7-Pad22)") (class "Default")
      (node (ref "U1") (pin "22") (pinfunction "ADC7_22") (pintype "input"))
    )
    (net (code "62") (name "unconnected-(U1-PB0-Pad12)") (class "Default")
      (node (ref "U1") (pin "12") (pinfunction "PB0_12") (pintype "bidirectional"))
    )
    (net (code "63") (name "unconnected-(U1-PB6-Pad7)") (class "Default")
      (node (ref "U1") (pin "7") (pinfunction "PB6_7") (pintype "bidirectional"))
    )
    (net (code "64") (name "unconnected-(U1-PB7-Pad8)") (class "Default")
      (node (ref "U1") (pin "8") (pinfunction "PB7_8") (pintype "bidirectional"))
    )
    (net (code "65") (name "unconnected-(U1-PC2-Pad25)") (class "Default")
      (node (ref "U1") (pin "25") (pinfunction "PC2_25") (pintype "bidirectional"))
    )
    (net (code "66") (name "unconnected-(U1-PC3-Pad26)") (class "Default")
      (node (ref "U1") (pin "26") (pinfunction "PC3_26") (pintype "bidirectional"))
    )
    (net (code "67") (name "unconnected-(U1-PC4-Pad27)") (class "Default")
      (node (ref "U1") (pin "27") (pinfunction "PC4_27") (pintype "bidirectional"))
    )
    (net (code "68") (name "unconnected-(U1-PC5-Pad28)") (class "Default")
      (node (ref "U1") (pin "28") (pinfunction "PC5_28") (pintype "bidirectional"))
    )
    (net (code "69") (name "unconnected-(U1-PD4-Pad2)") (class "Default")
      (node (ref "U1") (pin "2") (pinfunction "PD4_2") (pintype "bidirectional"))
    )
    (net (code "70") (name "unconnected-(U1-PD7-Pad11)") (class "Default")
      (node (ref "U1") (pin "11") (pinfunction "PD7_11") (pintype "bidirectional"))
    )
  )
)
